# Remote.net
KiCad netlist of a schematic drawn in EAGLE
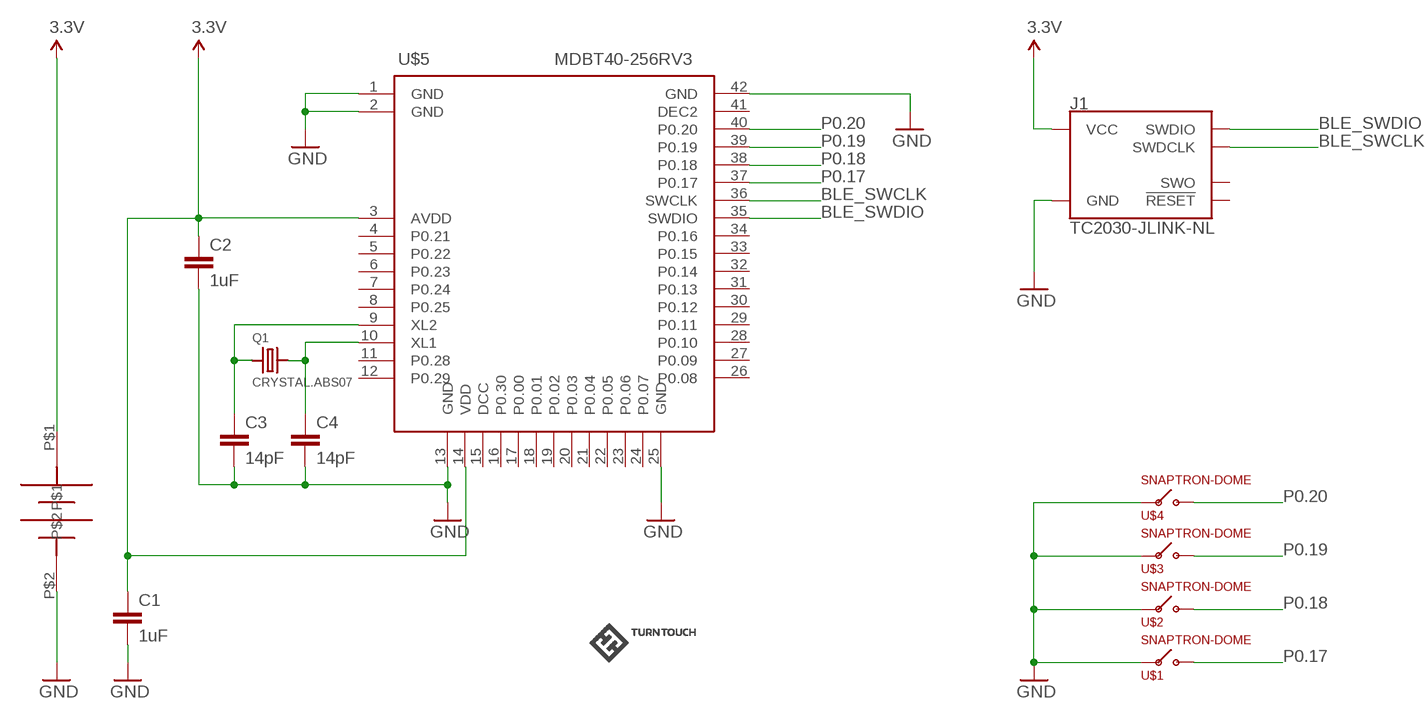
[diagram p0: schematic, sheet 1]

(export (version "E")
  (design (tool "Eeschema 10.0.6"))
  (components
    (comp (ref "C1")
      (value "1uF")
      (footprint "eagle-import:0603-CAP")
      (libsource (lib "eagle-import") (part "0.1UF-25V(+80/-20%)(0603)"))
    )
    (comp (ref "C2")
      (value "1uF")
      (footprint "eagle-import:0603-CAP")
      (libsource (lib "eagle-import") (part "0.1UF-25V(+80/-20%)(0603)"))
    )
    (comp (ref "C3")
      (value "14pF")
      (footprint "eagle-import:0603-CAP")
      (libsource (lib "eagle-import") (part "0.1UF-25V(+80/-20%)(0603)"))
    )
    (comp (ref "C4")
      (value "14pF")
      (footprint "eagle-import:0603-CAP")
      (libsource (lib "eagle-import") (part "0.1UF-25V(+80/-20%)(0603)"))
    )
    (comp (ref "J1")
      (value "TC2030-JLINK-NL")
      (footprint "eagle-import:TC2030-IDC-NL")
      (libsource (lib "eagle-import") (part "TC2030-JLINK-NL"))
    )
    (comp (ref "LOGO")
      (value "TURNTOUCHLOGO200DPI")
      (footprint "eagle-import:LOGO")
      (libsource (lib "eagle-import") (part "TURNTOUCHLOGO200DPI"))
    )
    (comp (ref "Q1")
      (value "CRYSTAL.ABS07")
      (footprint "eagle-import:ABS07")
      (libsource (lib "eagle-import") (part "CRYSTAL.ABS07"))
    )
    (comp (ref "U$1")
      (value "SNAPTRON-DOME")
      (footprint "eagle-import:DOME-M-SERIES")
      (libsource (lib "eagle-import") (part "SNAPTRON-DOME"))
    )
    (comp (ref "U$2")
      (value "SNAPTRON-DOME")
      (footprint "eagle-import:DOME-M-SERIES")
      (libsource (lib "eagle-import") (part "SNAPTRON-DOME"))
    )
    (comp (ref "U$3")
      (value "SNAPTRON-DOME")
      (footprint "eagle-import:DOME-M-SERIES")
      (libsource (lib "eagle-import") (part "SNAPTRON-DOME"))
    )
    (comp (ref "U$4")
      (value "SNAPTRON-DOME")
      (footprint "eagle-import:DOME-M-SERIES")
      (libsource (lib "eagle-import") (part "SNAPTRON-DOME"))
    )
    (comp (ref "U$5")
      (value "MDBT40-256RV3")
      (footprint "eagle-import:MDBT40")
      (libsource (lib "eagle-import") (part "MDBT40SMD"))
    )
    (comp (ref "U$6")
      (value "COINCELLHOLDER")
      (footprint "eagle-import:20MMCOINCELL")
      (libsource (lib "eagle-import") (part "COINCELLHOLDER"))
    )
  )
  (nets
    (net (code "1") (name "/BLE_SWCLK") (class "Default")
      (node (ref "J1") (pin "4") (pinfunction "SWDCLK_4") (pintype "bidirectional"))
      (node (ref "U$5") (pin "36") (pinfunction "SWCLK_36") (pintype "bidirectional"))
    )
    (net (code "2") (name "/BLE_SWDIO") (class "Default")
      (node (ref "J1") (pin "2") (pinfunction "SWDIO_2") (pintype "bidirectional"))
      (node (ref "U$5") (pin "35") (pinfunction "SWDIO_35") (pintype "bidirectional"))
    )
    (net (code "3") (name "/P0.17") (class "Default")
      (node (ref "U$1") (pin "P$3") (pinfunction "B_P$3") (pintype "bidirectional"))
      (node (ref "U$5") (pin "37") (pinfunction "P0.17_37") (pintype "bidirectional"))
    )
    (net (code "4") (name "/P0.18") (class "Default")
      (node (ref "U$2") (pin "P$3") (pinfunction "B_P$3") (pintype "bidirectional"))
      (node (ref "U$5") (pin "38") (pinfunction "P0.18_38") (pintype "bidirectional"))
    )
    (net (code "5") (name "/P0.19") (class "Default")
      (node (ref "U$3") (pin "P$3") (pinfunction "B_P$3") (pintype "bidirectional"))
      (node (ref "U$5") (pin "39") (pinfunction "P0.19_39") (pintype "bidirectional"))
    )
    (net (code "6") (name "/P0.20") (class "Default")
      (node (ref "U$4") (pin "P$3") (pinfunction "B_P$3") (pintype "bidirectional"))
      (node (ref "U$5") (pin "40") (pinfunction "P0.20_40") (pintype "bidirectional"))
    )
    (net (code "7") (name "3.3V") (class "Default")
      (node (ref "C1") (pin "1") (pinfunction "1_1") (pintype "passive"))
      (node (ref "C2") (pin "1") (pinfunction "1_1") (pintype "passive"))
      (node (ref "J1") (pin "1") (pinfunction "VCC_1") (pintype "bidirectional"))
      (node (ref "U$5") (pin "14") (pinfunction "VDD_14") (pintype "bidirectional"))
      (node (ref "U$5") (pin "3") (pinfunction "AVDD_3") (pintype "bidirectional"))
      (node (ref "U$6") (pin "P$1") (pinfunction "P$1_P$1") (pintype "bidirectional"))
    )
    (net (code "8") (name "GND") (class "Default")
      (node (ref "C1") (pin "2") (pinfunction "2_2") (pintype "passive"))
      (node (ref "C2") (pin "2") (pinfunction "2_2") (pintype "passive"))
      (node (ref "C3") (pin "2") (pinfunction "2_2") (pintype "passive"))
      (node (ref "C4") (pin "2") (pinfunction "2_2") (pintype "passive"))
      (node (ref "J1") (pin "5") (pinfunction "GND_5") (pintype "bidirectional"))
      (node (ref "U$1") (pin "P$1") (pinfunction "V_P$1") (pintype "bidirectional"))
      (node (ref "U$1") (pin "P$2") (pinfunction "V_P$2") (pintype "bidirectional"))
      (node (ref "U$2") (pin "P$1") (pinfunction "V_P$1") (pintype "bidirectional"))
      (node (ref "U$2") (pin "P$2") (pinfunction "V_P$2") (pintype "bidirectional"))
      (node (ref "U$3") (pin "P$1") (pinfunction "V_P$1") (pintype "bidirectional"))
      (node (ref "U$3") (pin "P$2") (pinfunction "V_P$2") (pintype "bidirectional"))
      (node (ref "U$4") (pin "P$1") (pinfunction "V_P$1") (pintype "bidirectional"))
      (node (ref "U$4") (pin "P$2") (pinfunction "V_P$2") (pintype "bidirectional"))
      (node (ref "U$5") (pin "1") (pinfunction "GND_1") (pintype "bidirectional"))
      (node (ref "U$5") (pin "13") (pinfunction "GND_13") (pintype "bidirectional"))
      (node (ref "U$5") (pin "2") (pinfunction "GND_2") (pintype "bidirectional"))
      (node (ref "U$5") (pin "25") (pinfunction "GND_25") (pintype "bidirectional"))
      (node (ref "U$5") (pin "42") (pinfunction "GND_42") (pintype "bidirectional"))
      (node (ref "U$6") (pin "P$2") (pinfunction "P$2_P$2") (pintype "bidirectional"))
    )
    (net (code "9") (name "Net-(U$5-XL1)") (class "Default")
      (node (ref "C4") (pin "1") (pinfunction "1_1") (pintype "passive"))
      (node (ref "Q1") (pin "2") (pinfunction "2_2") (pintype "passive"))
      (node (ref "U$5") (pin "10") (pinfunction "XL1_10") (pintype "bidirectional"))
    )
    (net (code "10") (name "Net-(U$5-XL2)") (class "Default")
      (node (ref "C3") (pin "1") (pinfunction "1_1") (pintype "passive"))
      (node (ref "Q1") (pin "1") (pinfunction "1_1") (pintype "passive"))
      (node (ref "U$5") (pin "9") (pinfunction "XL2_9") (pintype "bidirectional"))
    )
    (net (code "11") (name "unconnected-(J1-SWO-Pad6)") (class "Default")
      (node (ref "J1") (pin "6") (pinfunction "SWO_6") (pintype "bidirectional"))
    )
    (net (code "12") (name "unconnected-(J1-~{RESET}-Pad3)") (class "Default")
      (node (ref "J1") (pin "3") (pinfunction "~{RESET}_3") (pintype "bidirectional"))
    )
    (net (code "13") (name "unconnected-(U$5-DCC-Pad15)") (class "Default")
      (node (ref "U$5") (pin "15") (pinfunction "DCC_15") (pintype "bidirectional"))
    )
    (net (code "14") (name "unconnected-(U$5-DEC2-Pad41)") (class "Default")
      (node (ref "U$5") (pin "41") (pinfunction "DEC2_41") (pintype "bidirectional"))
    )
    (net (code "15") (name "unconnected-(U$5-P0.00-Pad17)") (class "Default")
      (node (ref "U$5") (pin "17") (pinfunction "P0.00_17") (pintype "bidirectional"))
    )
    (net (code "16") (name "unconnected-(U$5-P0.01-Pad18)") (class "Default")
      (node (ref "U$5") (pin "18") (pinfunction "P0.01_18") (pintype "bidirectional"))
    )
    (net (code "17") (name "unconnected-(U$5-P0.02-Pad19)") (class "Default")
      (node (ref "U$5") (pin "19") (pinfunction "P0.02_19") (pintype "bidirectional"))
    )
    (net (code "18") (name "unconnected-(U$5-P0.03-Pad20)") (class "Default")
      (node (ref "U$5") (pin "20") (pinfunction "P0.03_20") (pintype "bidirectional"))
    )
    (net (code "19") (name "unconnected-(U$5-P0.04-Pad21)") (class "Default")
      (node (ref "U$5") (pin "21") (pinfunction "P0.04_21") (pintype "bidirectional"))
    )
    (net (code "20") (name "unconnected-(U$5-P0.05-Pad22)") (class "Default")
      (node (ref "U$5") (pin "22") (pinfunction "P0.05_22") (pintype "bidirectional"))
    )
    (net (code "21") (name "unconnected-(U$5-P0.06-Pad23)") (class "Default")
      (node (ref "U$5") (pin "23") (pinfunction "P0.06_23") (pintype "bidirectional"))
    )
    (net (code "22") (name "unconnected-(U$5-P0.07-Pad24)") (class "Default")
      (node (ref "U$5") (pin "24") (pinfunction "P0.07_24") (pintype "bidirectional"))
    )
    (net (code "23") (name "unconnected-(U$5-P0.08-Pad26)") (class "Default")
      (node (ref "U$5") (pin "26") (pinfunction "P0.08_26") (pintype "bidirectional"))
    )
    (net (code "24") (name "unconnected-(U$5-P0.09-Pad27)") (class "Default")
      (node (ref "U$5") (pin "27") (pinfunction "P0.09_27") (pintype "bidirectional"))
    )
    (net (code "25") (name "unconnected-(U$5-P0.10-Pad28)") (class "Default")
      (node (ref "U$5") (pin "28") (pinfunction "P0.10_28") (pintype "bidirectional"))
    )
    (net (code "26") (name "unconnected-(U$5-P0.11-Pad29)") (class "Default")
      (node (ref "U$5") (pin "29") (pinfunction "P0.11_29") (pintype "bidirectional"))
    )
    (net (code "27") (name "unconnected-(U$5-P0.12-Pad30)") (class "Default")
      (node (ref "U$5") (pin "30") (pinfunction "P0.12_30") (pintype "bidirectional"))
    )
    (net (code "28") (name "unconnected-(U$5-P0.13-Pad31)") (class "Default")
      (node (ref "U$5") (pin "31") (pinfunction "P0.13_31") (pintype "bidirectional"))
    )
    (net (code "29") (name "unconnected-(U$5-P0.14-Pad32)") (class "Default")
      (node (ref "U$5") (pin "32") (pinfunction "P0.14_32") (pintype "bidirectional"))
    )
    (net (code "30") (name "unconnected-(U$5-P0.15-Pad33)") (class "Default")
      (node (ref "U$5") (pin "33") (pinfunction "P0.15_33") (pintype "bidirectional"))
    )
    (net (code "31") (name "unconnected-(U$5-P0.16-Pad34)") (class "Default")
      (node (ref "U$5") (pin "34") (pinfunction "P0.16_34") (pintype "bidirectional"))
    )
    (net (code "32") (name "unconnected-(U$5-P0.21-Pad4)") (class "Default")
      (node (ref "U$5") (pin "4") (pinfunction "P0.21_4") (pintype "bidirectional"))
    )
    (net (code "33") (name "unconnected-(U$5-P0.22-Pad5)") (class "Default")
      (node (ref "U$5") (pin "5") (pinfunction "P0.22_5") (pintype "bidirectional"))
    )
    (net (code "34") (name "unconnected-(U$5-P0.23-Pad6)") (class "Default")
      (node (ref "U$5") (pin "6") (pinfunction "P0.23_6") (pintype "bidirectional"))
    )
    (net (code "35") (name "unconnected-(U$5-P0.24-Pad7)") (class "Default")
      (node (ref "U$5") (pin "7") (pinfunction "P0.24_7") (pintype "bidirectional"))
    )
    (net (code "36") (name "unconnected-(U$5-P0.25-Pad8)") (class "Default")
      (node (ref "U$5") (pin "8") (pinfunction "P0.25_8") (pintype "bidirectional"))
    )
    (net (code "37") (name "unconnected-(U$5-P0.28-Pad11)") (class "Default")
      (node (ref "U$5") (pin "11") (pinfunction "P0.28_11") (pintype "bidirectional"))
    )
    (net (code "38") (name "unconnected-(U$5-P0.29-Pad12)") (class "Default")
      (node (ref "U$5") (pin "12") (pinfunction "P0.29_12") (pintype "bidirectional"))
    )
    (net (code "39") (name "unconnected-(U$5-P0.30-Pad16)") (class "Default")
      (node (ref "U$5") (pin "16") (pinfunction "P0.30_16") (pintype "bidirectional"))
    )
  )
)
